# LIXIE_II_Main_V2.net
KiCad netlist of a schematic drawn in EAGLE
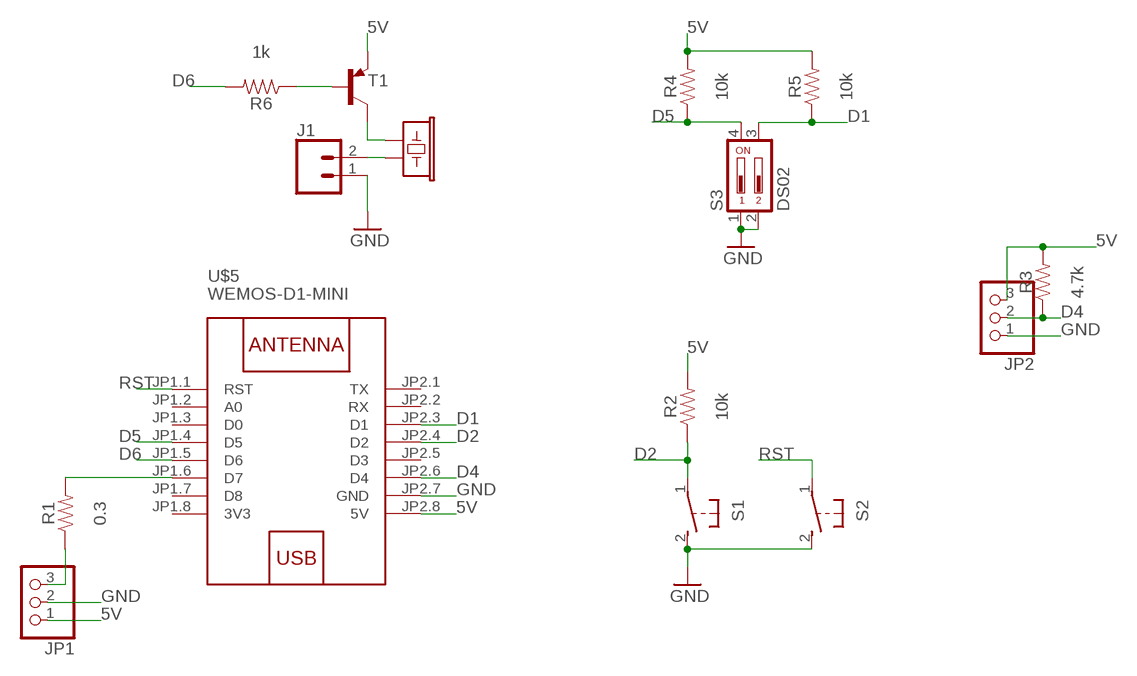
[diagram p0: schematic, sheet 1]

(export (version "E")
  (design (tool "Eeschema 10.0.6"))
  (components
    (comp (ref "J1")
      (value "CONN_02")
      (footprint "eagle-import:1X02")
      (libsource (lib "eagle-import") (part "CONN_02"))
    )
    (comp (ref "JP1")
      (value "PINHD-1X3")
      (footprint "eagle-import:1X03")
      (libsource (lib "eagle-import") (part "PINHD-1X3"))
    )
    (comp (ref "JP2")
      (value "PINHD-1X3")
      (footprint "eagle-import:1X03")
      (libsource (lib "eagle-import") (part "PINHD-1X3"))
    )
    (comp (ref "LS2")
      (value "BUZZER-PTH")
      (footprint "eagle-import:BUZZER-12MM")
      (libsource (lib "eagle-import") (part "BUZZER-PTH"))
    )
    (comp (ref "R1")
      (value "0.3")
      (footprint "eagle-import:0805")
      (libsource (lib "eagle-import") (part "0.3OHM-0805-1/8W-1%"))
    )
    (comp (ref "R2")
      (value "10k")
      (footprint "eagle-import:0805")
      (libsource (lib "eagle-import") (part "0.3OHM-0805-1/8W-1%"))
    )
    (comp (ref "R3")
      (value "4.7k")
      (footprint "eagle-import:0805")
      (libsource (lib "eagle-import") (part "0.3OHM-0805-1/8W-1%"))
    )
    (comp (ref "R4")
      (value "10k")
      (footprint "eagle-import:0805")
      (libsource (lib "eagle-import") (part "0.3OHM-0805-1/8W-1%"))
    )
    (comp (ref "R5")
      (value "10k")
      (footprint "eagle-import:0805")
      (libsource (lib "eagle-import") (part "0.3OHM-0805-1/8W-1%"))
    )
    (comp (ref "R6")
      (value "1k")
      (footprint "eagle-import:0805")
      (libsource (lib "eagle-import") (part "0.3OHM-0805-1/8W-1%"))
    )
    (comp (ref "S1")
      (value "31-XX")
      (footprint "eagle-import:B3F-31XX")
      (libsource (lib "eagle-import") (part "31-XX"))
    )
    (comp (ref "S2")
      (value "31-XX")
      (footprint "eagle-import:B3F-31XX")
      (libsource (lib "eagle-import") (part "31-XX"))
    )
    (comp (ref "S3")
      (value "DS02")
      (footprint "eagle-import:DS-02")
      (fields (field (name "MPN") "MCNDS02"))
      (libsource (lib "eagle-import") (part "DS02"))
    )
    (comp (ref "T1")
      (value "-PNP-SOT23-EBC")
      (footprint "eagle-import:SOT23-EBC")
      (libsource (lib "eagle-import") (part "-PNP-SOT23-EBC"))
    )
    (comp (ref "U$5")
      (value "WEMOS-D1-MINI")
      (footprint "eagle-import:WEMOS-D1-MINI")
      (libsource (lib "eagle-import") (part "WEMOS-D1-MINI"))
    )
  )
  (nets
    (net (code "1") (name "/3V3") (class "Default")
      (node (ref "U$5") (pin "JP1.8") (pinfunction "3V3_JP1.8") (pintype "power_in"))
    )
    (net (code "2") (name "/5V") (class "Default")
      (node (ref "JP1") (pin "1") (pinfunction "1_1") (pintype "passive"))
      (node (ref "JP2") (pin "3") (pinfunction "3_3") (pintype "passive"))
      (node (ref "R2") (pin "2") (pinfunction "2_2") (pintype "passive"))
      (node (ref "R3") (pin "2") (pinfunction "2_2") (pintype "passive"))
      (node (ref "R4") (pin "2") (pinfunction "2_2") (pintype "passive"))
      (node (ref "R5") (pin "2") (pinfunction "2_2") (pintype "passive"))
      (node (ref "T1") (pin "E") (pinfunction "E_E") (pintype "passive"))
      (node (ref "U$5") (pin "JP2.8") (pinfunction "5V_JP2.8") (pintype "power_in"))
    )
    (net (code "3") (name "/D1") (class "Default")
      (node (ref "R5") (pin "1") (pinfunction "1_1") (pintype "passive"))
      (node (ref "S3") (pin "3") (pinfunction "3_3") (pintype "passive"))
      (node (ref "U$5") (pin "JP2.3") (pinfunction "D1_JP2.3") (pintype "bidirectional"))
    )
    (net (code "4") (name "/D2") (class "Default")
      (node (ref "R2") (pin "1") (pinfunction "1_1") (pintype "passive"))
      (node (ref "S1") (pin "1") (pinfunction "P_1") (pintype "passive"))
      (node (ref "U$5") (pin "JP2.4") (pinfunction "D2_JP2.4") (pintype "bidirectional"))
    )
    (net (code "5") (name "/D4") (class "Default")
      (node (ref "JP2") (pin "2") (pinfunction "2_2") (pintype "passive"))
      (node (ref "R3") (pin "1") (pinfunction "1_1") (pintype "passive"))
      (node (ref "U$5") (pin "JP2.6") (pinfunction "D4_JP2.6") (pintype "bidirectional"))
    )
    (net (code "6") (name "/D5") (class "Default")
      (node (ref "R4") (pin "1") (pinfunction "1_1") (pintype "passive"))
      (node (ref "S3") (pin "4") (pinfunction "4_4") (pintype "passive"))
      (node (ref "U$5") (pin "JP1.4") (pinfunction "D5_JP1.4") (pintype "bidirectional"))
    )
    (net (code "7") (name "/D6") (class "Default")
      (node (ref "R6") (pin "2") (pinfunction "2_2") (pintype "passive"))
      (node (ref "U$5") (pin "JP1.5") (pinfunction "D6_JP1.5") (pintype "bidirectional"))
    )
    (net (code "8") (name "/RST") (class "Default")
      (node (ref "S2") (pin "1") (pinfunction "P_1") (pintype "passive"))
      (node (ref "U$5") (pin "JP1.1") (pinfunction "RST_JP1.1") (pintype "bidirectional"))
    )
    (net (code "9") (name "GND") (class "Default")
      (node (ref "J1") (pin "1") (pinfunction "1_1") (pintype "passive"))
      (node (ref "JP1") (pin "2") (pinfunction "2_2") (pintype "passive"))
      (node (ref "JP2") (pin "1") (pinfunction "1_1") (pintype "passive"))
      (node (ref "S1") (pin "2") (pinfunction "S_2") (pintype "passive"))
      (node (ref "S2") (pin "2") (pinfunction "S_2") (pintype "passive"))
      (node (ref "S3") (pin "1") (pinfunction "1_1") (pintype "passive"))
      (node (ref "S3") (pin "2") (pinfunction "2_2") (pintype "passive"))
      (node (ref "U$5") (pin "JP2.7") (pinfunction "GND_JP2.7") (pintype "power_in"))
    )
    (net (code "10") (name "Net-(JP1-Pad3)") (class "Default")
      (node (ref "JP1") (pin "3") (pinfunction "3_3") (pintype "passive"))
      (node (ref "R1") (pin "1") (pinfunction "1_1") (pintype "passive"))
    )
    (net (code "11") (name "Net-(LS2-1)") (class "Default")
      (node (ref "LS2") (pin "+") (pinfunction "1_+") (pintype "passive"))
      (node (ref "T1") (pin "C") (pinfunction "C_C") (pintype "passive"))
    )
    (net (code "12") (name "Net-(LS2-2)") (class "Default")
      (node (ref "J1") (pin "2") (pinfunction "2_2") (pintype "passive"))
      (node (ref "LS2") (pin "-") (pinfunction "2_-") (pintype "passive"))
    )
    (net (code "13") (name "Net-(R6-Pad1)") (class "Default")
      (node (ref "R6") (pin "1") (pinfunction "1_1") (pintype "passive"))
      (node (ref "T1") (pin "B") (pinfunction "B_B") (pintype "passive"))
    )
    (net (code "14") (name "Net-(U$5-D7)") (class "Default")
      (node (ref "R1") (pin "2") (pinfunction "2_2") (pintype "passive"))
      (node (ref "U$5") (pin "JP1.6") (pinfunction "D7_JP1.6") (pintype "bidirectional"))
    )
    (net (code "15") (name "unconnected-(U$5-A0-PadJP1.2)") (class "Default")
      (node (ref "U$5") (pin "JP1.2") (pinfunction "A0_JP1.2") (pintype "bidirectional"))
    )
    (net (code "16") (name "unconnected-(U$5-D0-PadJP1.3)") (class "Default")
      (node (ref "U$5") (pin "JP1.3") (pinfunction "D0_JP1.3") (pintype "bidirectional"))
    )
    (net (code "17") (name "unconnected-(U$5-D3-PadJP2.5)") (class "Default")
      (node (ref "U$5") (pin "JP2.5") (pinfunction "D3_JP2.5") (pintype "bidirectional"))
    )
    (net (code "18") (name "unconnected-(U$5-D8-PadJP1.7)") (class "Default")
      (node (ref "U$5") (pin "JP1.7") (pinfunction "D8_JP1.7") (pintype "bidirectional"))
    )
    (net (code "19") (name "unconnected-(U$5-RX-PadJP2.2)") (class "Default")
      (node (ref "U$5") (pin "JP2.2") (pinfunction "RX_JP2.2") (pintype "bidirectional"))
    )
    (net (code "20") (name "unconnected-(U$5-TX-PadJP2.1)") (class "Default")
      (node (ref "U$5") (pin "JP2.1") (pinfunction "TX_JP2.1") (pintype "bidirectional"))
    )
  )
)
